# CANbus.net
KiCad netlist of a schematic drawn in Altium Designer
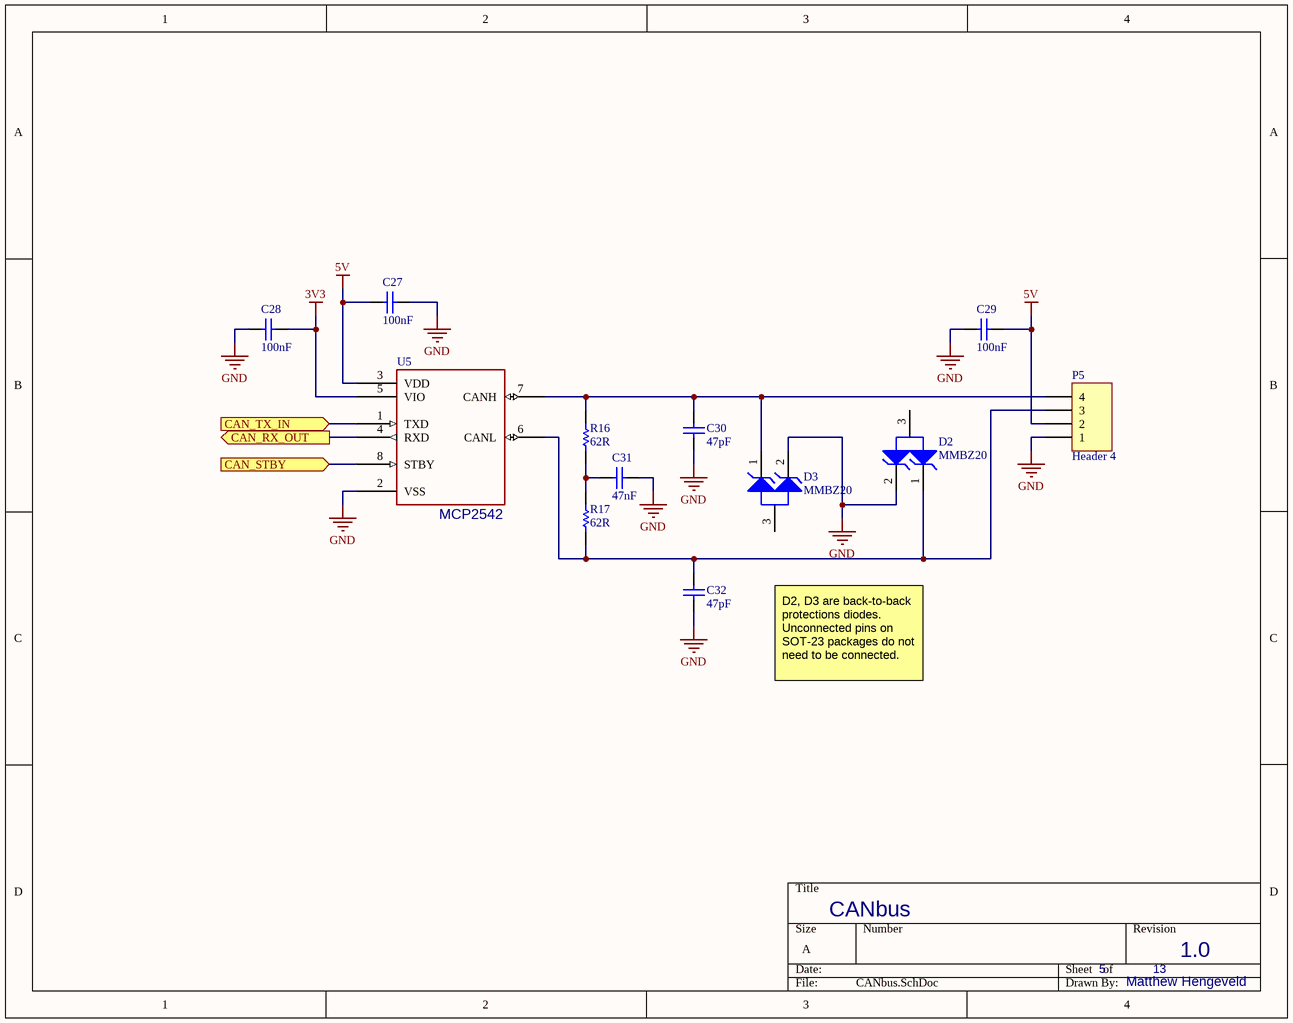
[diagram p0: CANbus.SchDoc]

(export (version "E")
  (design (tool "Eeschema 10.0.6"))
  (components
    (comp (ref "C27")
      (value "100nF")
      (footprint "CAPC1608X92X38LL15T08")
      (fields (field (name "PART NUMBER") "VJ0603Y104KNXAO") (field (name "MANUFACTURER") "Vitramon"))
      (libsource (lib "Altium Content Vault") (part "CAP"))
    )
    (comp (ref "C28")
      (value "100nF")
      (footprint "CAPC1608X92X38LL15T08")
      (fields (field (name "PART NUMBER") "VJ0603Y104KNXAO") (field (name "MANUFACTURER") "Vitramon"))
      (libsource (lib "Altium Content Vault") (part "CAP"))
    )
    (comp (ref "C29")
      (value "100nF")
      (footprint "CAPC1608X92X38LL15T08")
      (fields (field (name "PART NUMBER") "VJ0603Y104KNXAO") (field (name "MANUFACTURER") "Vitramon"))
      (libsource (lib "Altium Content Vault") (part "CAP"))
    )
    (comp (ref "C30")
      (value "47pF")
      (footprint "CAPC1608X87X35LL15T15")
      (fields (field (name "MANUFACTURER") "Kemet") (field (name "PART NUMBER") "C0603C470J1GACTU"))
      (libsource (lib "Altium Content Vault") (part "CAP"))
    )
    (comp (ref "C31")
      (value "47nF")
      (footprint "CAPC2013X88X50LL20T25")
      (fields (field (name "MANUFACTURER") "Kemet") (field (name "PART NUMBER") "C0805C473K3RACTU"))
      (libsource (lib "Altium Content Vault") (part "CAP"))
    )
    (comp (ref "C32")
      (value "47pF")
      (footprint "CAPC1608X87X35LL15T15")
      (fields (field (name "MANUFACTURER") "Kemet") (field (name "PART NUMBER") "C0603C470J1GACTU"))
      (libsource (lib "Altium Content Vault") (part "CAP"))
    )
    (comp (ref "D2")
      (value "MMBZ20")
      (footprint "SOT-23-3")
      (fields (field (name "PARTNUMBER") "SM12T1G") (field (name "MANUFACTURER") "On Semiconductor"))
      (libsource (lib "Hengeveld") (part "TVS Diode"))
    )
    (comp (ref "D3")
      (value "MMBZ20")
      (footprint "SOT-23-3")
      (fields (field (name "PARTNUMBER") "SM12T1G") (field (name "MANUFACTURER") "On Semiconductor"))
      (libsource (lib "Hengeveld") (part "TVS Diode"))
    )
    (comp (ref "P5")
      (value "Header 4")
      (footprint "HDR1X4")
      (description "Header, 4-Pin")
      (fields (field (name "PUBLISHER") "Altium Limited"))
      (libsource (lib "Hengeveld") (part "Header 4"))
    )
    (comp (ref "R16")
      (value "62R")
      (footprint "RESC3216X70X50LL05T20")
      (fields (field (name "PART NUMBER") "ERJ8CWFR024V") (field (name "MANUFACTURER") "Panasonic"))
      (libsource (lib "Altium Content Vault") (part "RES"))
    )
    (comp (ref "R17")
      (value "62R")
      (footprint "RESC3216X70X50LL05T20")
      (fields (field (name "PART NUMBER") "ERJ8CWFR024V") (field (name "MANUFACTURER") "Panasonic"))
      (libsource (lib "Altium Content Vault") (part "RES"))
    )
    (comp (ref "U5")
      (value "MCP2542")
      (footprint "MCHP-SOIC-SN8_N")
      (libsource (lib "Hengeveld") (part "MCP2542"))
    )
  )
  (nets
    (net (code "1") (name "/CAN_RX_OUT") (class "Default")
      (node (ref "U5") (pin "4") (pinfunction "RXD_4") (pintype "output"))
    )
    (net (code "2") (name "/CAN_STBY") (class "Default")
      (node (ref "U5") (pin "8") (pinfunction "STBY_8") (pintype "input"))
    )
    (net (code "3") (name "/CAN_TX_IN") (class "Default")
      (node (ref "U5") (pin "1") (pinfunction "TXD_1") (pintype "input"))
    )
    (net (code "4") (name "3V3") (class "Default")
      (node (ref "C28") (pin "2") (pinfunction "2_2") (pintype "passive"))
      (node (ref "U5") (pin "5") (pinfunction "VIO_5") (pintype "power_in"))
    )
    (net (code "5") (name "5V") (class "Default")
      (node (ref "C27") (pin "1") (pinfunction "1_1") (pintype "passive"))
      (node (ref "C29") (pin "2") (pinfunction "2_2") (pintype "passive"))
      (node (ref "P5") (pin "2") (pinfunction "2_2") (pintype "passive"))
      (node (ref "U5") (pin "3") (pinfunction "VDD_3") (pintype "power_in"))
    )
    (net (code "6") (name "GND") (class "Default")
      (node (ref "C27") (pin "2") (pinfunction "2_2") (pintype "passive"))
      (node (ref "C28") (pin "1") (pinfunction "1_1") (pintype "passive"))
      (node (ref "C29") (pin "1") (pinfunction "1_1") (pintype "passive"))
      (node (ref "C30") (pin "1") (pinfunction "1_1") (pintype "passive"))
      (node (ref "C31") (pin "2") (pinfunction "2_2") (pintype "passive"))
      (node (ref "C32") (pin "1") (pinfunction "1_1") (pintype "passive"))
      (node (ref "D2") (pin "2") (pinfunction "K2_2") (pintype "passive"))
      (node (ref "D3") (pin "2") (pinfunction "K2_2") (pintype "passive"))
      (node (ref "P5") (pin "1") (pinfunction "1_1") (pintype "passive"))
      (node (ref "U5") (pin "2") (pinfunction "VSS_2") (pintype "power_in"))
    )
    (net (code "7") (name "Net-(C31-Pad1)") (class "Default")
      (node (ref "C31") (pin "1") (pinfunction "1_1") (pintype "passive"))
      (node (ref "R16") (pin "1") (pinfunction "1_1") (pintype "passive"))
      (node (ref "R17") (pin "2") (pinfunction "2_2") (pintype "passive"))
    )
    (net (code "8") (name "Net-(D2-K1)") (class "Default")
      (node (ref "C32") (pin "2") (pinfunction "2_2") (pintype "passive"))
      (node (ref "D2") (pin "1") (pinfunction "K1_1") (pintype "passive"))
      (node (ref "P5") (pin "3") (pinfunction "3_3") (pintype "passive"))
      (node (ref "R17") (pin "1") (pinfunction "1_1") (pintype "passive"))
      (node (ref "U5") (pin "6") (pinfunction "CANL_6") (pintype "bidirectional"))
    )
    (net (code "9") (name "Net-(D3-K1)") (class "Default")
      (node (ref "C30") (pin "2") (pinfunction "2_2") (pintype "passive"))
      (node (ref "D3") (pin "1") (pinfunction "K1_1") (pintype "passive"))
      (node (ref "P5") (pin "4") (pinfunction "4_4") (pintype "passive"))
      (node (ref "R16") (pin "2") (pinfunction "2_2") (pintype "passive"))
      (node (ref "U5") (pin "7") (pinfunction "CANH_7") (pintype "bidirectional"))
    )
    (net (code "10") (name "unconnected-(D2-A-Pad3)") (class "Default")
      (node (ref "D2") (pin "3") (pinfunction "A_3") (pintype "passive"))
    )
    (net (code "11") (name "unconnected-(D3-A-Pad3)") (class "Default")
      (node (ref "D3") (pin "3") (pinfunction "A_3") (pintype "passive"))
    )
  )
)
